# Power.net
KiCad netlist of a schematic drawn in Altium Designer
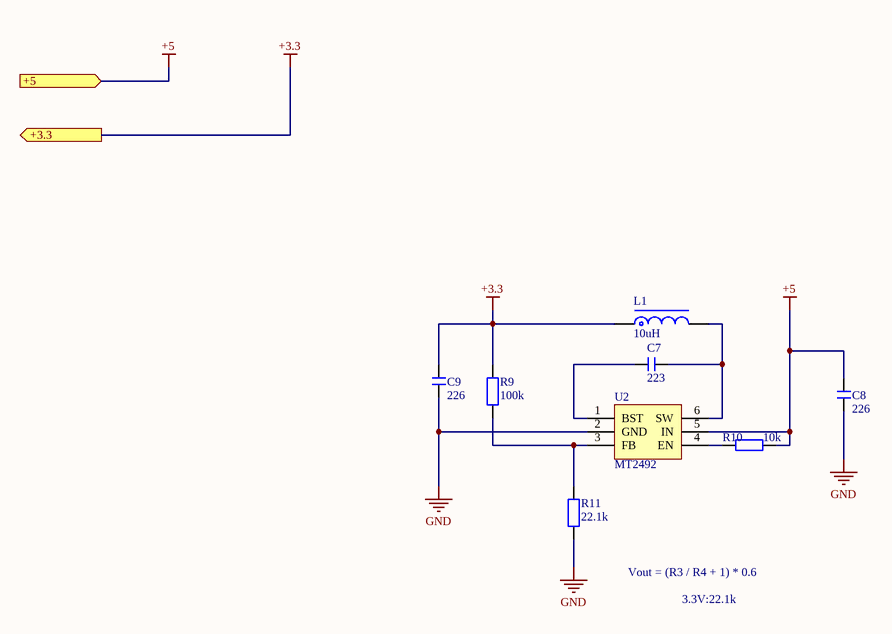
[diagram p0: Power.SchDoc]

(export (version "E")
  (design (tool "Eeschema 10.0.6"))
  (components
    (comp (ref "C7")
      (value "223")
      (footprint "C 0603-L")
      (description "贴片电容")
      (libsource (lib "0.1 - 电阻-电容-电感") (part "C"))
    )
    (comp (ref "C8")
      (value "226")
      (footprint "C 0805-L")
      (description "贴片电容")
      (libsource (lib "0.1 - 电阻-电容-电感") (part "C"))
    )
    (comp (ref "C9")
      (value "226")
      (footprint "C 0805-L")
      (description "贴片电容")
      (libsource (lib "0.1 - 电阻-电容-电感") (part "C"))
    )
    (comp (ref "L1")
      (value "10uH")
      (footprint "L 1206")
      (description "NR磁胶电感")
      (libsource (lib "0.1 - 电阻-电容-电感") (part "L-NR"))
    )
    (comp (ref "R9")
      (value "100k")
      (footprint "R 0603_L")
      (description "贴片电阻")
      (libsource (lib "0.1 - 电阻-电容-电感") (part "R"))
    )
    (comp (ref "R10")
      (value "10k")
      (footprint "R 0603_L")
      (description "贴片电阻")
      (libsource (lib "0.1 - 电阻-电容-电感") (part "R"))
    )
    (comp (ref "R11")
      (value "22.1k")
      (footprint "R 0603_L")
      (description "贴片电阻")
      (libsource (lib "0.1 - 电阻-电容-电感") (part "R"))
    )
    (comp (ref "U2")
      (value "MT2492")
      (footprint "SOT23-6N")
      (description "DC降压芯片")
      (libsource (lib "1.0 - 电源类芯片") (part "MP2359"))
    )
  )
  (nets
    (net (code "1") (name "+3.3") (class "Default")
      (node (ref "C9") (pin "1") (pinfunction "1_1") (pintype "passive"))
      (node (ref "L1") (pin "1") (pinfunction "1_1") (pintype "passive"))
      (node (ref "R9") (pin "1") (pinfunction "1_1") (pintype "passive"))
    )
    (net (code "2") (name "+5") (class "Default")
      (node (ref "C8") (pin "1") (pinfunction "1_1") (pintype "passive"))
      (node (ref "R10") (pin "2") (pinfunction "2_2") (pintype "passive"))
      (node (ref "U2") (pin "5") (pinfunction "IN_5") (pintype "passive"))
    )
    (net (code "3") (name "GND") (class "Default")
      (node (ref "C8") (pin "2") (pinfunction "2_2") (pintype "passive"))
      (node (ref "C9") (pin "2") (pinfunction "2_2") (pintype "passive"))
      (node (ref "R11") (pin "1") (pinfunction "1_1") (pintype "passive"))
      (node (ref "U2") (pin "2") (pinfunction "GND_2") (pintype "passive"))
    )
    (net (code "4") (name "Net-(U2-BST)") (class "Default")
      (node (ref "C7") (pin "2") (pinfunction "2_2") (pintype "passive"))
      (node (ref "U2") (pin "1") (pinfunction "BST_1") (pintype "passive"))
    )
    (net (code "5") (name "Net-(U2-EN)") (class "Default")
      (node (ref "R10") (pin "1") (pinfunction "1_1") (pintype "passive"))
      (node (ref "U2") (pin "4") (pinfunction "EN_4") (pintype "passive"))
    )
    (net (code "6") (name "Net-(U2-FB)") (class "Default")
      (node (ref "R11") (pin "2") (pinfunction "2_2") (pintype "passive"))
      (node (ref "R9") (pin "2") (pinfunction "2_2") (pintype "passive"))
      (node (ref "U2") (pin "3") (pinfunction "FB_3") (pintype "passive"))
    )
    (net (code "7") (name "Net-(U2-SW)") (class "Default")
      (node (ref "C7") (pin "1") (pinfunction "1_1") (pintype "passive"))
      (node (ref "L1") (pin "2") (pinfunction "2_2") (pintype "passive"))
      (node (ref "U2") (pin "6") (pinfunction "SW_6") (pintype "passive"))
    )
  )
)
